# ALL_COMPONENTS.net
KiCad netlist of a schematic drawn in Altium Designer
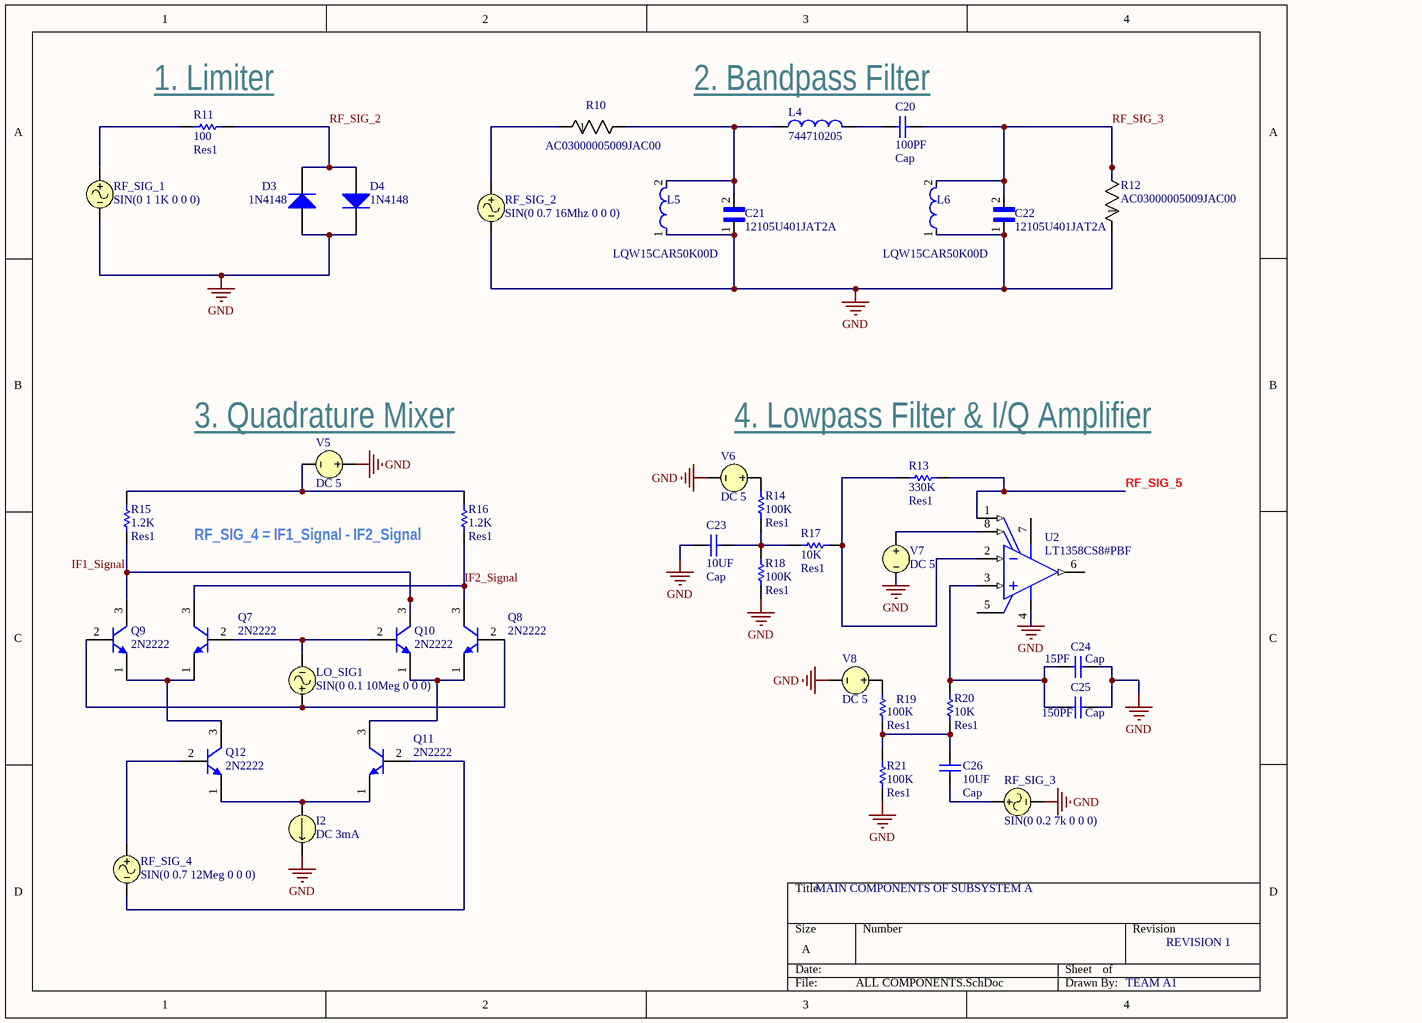
[diagram p0: ALL COMPONENTS.SchDoc]

(export (version "E")
  (design (tool "Eeschema 10.0.6"))
  (components
    (comp (ref "C20")
      (value "Cap")
      (footprint "RADIAL-0.1")
      (description "Capacitor")
      (fields
        (field (name "ALTIUM_VALUE") "100PF")
        (field (name "MANUFACTURER PART NUMBER") "K101K15C0GF53L2")
        (field (name "PUBLISHER") "Altium Limited")
      )
      (libsource (lib "ECE295-Capacitors-TH") (part "CAP CER 100PF 50V C0G/NP0 RADIAL"))
    )
    (comp (ref "C21")
      (value "12105U401JAT2A")
      (footprint "CAPC3224X140N")
      (description "CAP CER 400PF 50V 5% NP0 1210")
      (libsource (lib "12105U401JAT2A") (part "12105U401JAT2A"))
    )
    (comp (ref "C22")
      (value "12105U401JAT2A")
      (footprint "CAPC3224X140N")
      (description "CAP CER 400PF 50V 5% NP0 1210")
      (libsource (lib "12105U401JAT2A") (part "12105U401JAT2A"))
    )
    (comp (ref "C23")
      (value "Cap")
      (footprint "RADIAL-0.1")
      (description "Capacitor")
      (fields
        (field (name "ALTIUM_VALUE") "10UF")
        (field (name "MANUFACTURER PART NUMBER") "ESK106M063AC3FA")
        (field (name "PUBLISHER") "Altium Limited")
      )
      (libsource (lib "ECE295-Capacitors-TH") (part "CAP ALUM 10UF 20% 63V RADIAL"))
    )
    (comp (ref "C24")
      (value "Cap")
      (footprint "RADIAL-0.1")
      (description "Capacitor")
      (fields
        (field (name "ALTIUM_VALUE") "15PF")
        (field (name "MANUFACTURER PART NUMBER") "K150J15C0GF5TL2")
        (field (name "PUBLISHER") "Altium Limited")
      )
      (libsource (lib "ECE295-Capacitors-TH") (part "CAP CER 15PF 50V C0G/NP0 RADIAL"))
    )
    (comp (ref "C25")
      (value "Cap")
      (footprint "RADIAL-0.1")
      (description "Capacitor")
      (fields
        (field (name "ALTIUM_VALUE") "150PF")
        (field (name "MANUFACTURER PART NUMBER") "K151J15C0GF53L2")
        (field (name "PUBLISHER") "Altium Limited")
      )
      (libsource (lib "ECE295-Capacitors-TH") (part "CAP CER 150PF 50V C0G/NP0 RADIAL"))
    )
    (comp (ref "C26")
      (value "Cap")
      (footprint "RADIAL-0.1")
      (description "Capacitor")
      (fields
        (field (name "ALTIUM_VALUE") "10UF")
        (field (name "MANUFACTURER PART NUMBER") "ESK106M063AC3FA")
        (field (name "PUBLISHER") "Altium Limited")
      )
      (libsource (lib "ECE295-Capacitors-TH") (part "CAP ALUM 10UF 20% 63V RADIAL"))
    )
    (comp (ref "D3")
      (value "1N4148")
      (footprint "NXP-SOD27-2_V")
      (description "High-speed Diode, 100 V, 450 mA, 2-Pin SOD27, RoHS")
      (fields (field (name "MANUFACTURER") "NXP Semiconductors"))
      (libsource (lib "Altium Content Vault") (part "NXP-A1K2-2"))
    )
    (comp (ref "D4")
      (value "1N4148")
      (footprint "NXP-SOD27-2_V")
      (description "High-speed Diode, 100 V, 450 mA, 2-Pin SOD27, RoHS")
      (fields (field (name "MANUFACTURER") "NXP Semiconductors"))
      (libsource (lib "Altium Content Vault") (part "NXP-A1K2-2"))
    )
    (comp (ref "I2")
      (value "DC 3mA")
      (description "Current Source")
      (fields (field (name "PUBLISHER") "Altium Limited"))
      (libsource (lib "Simulation Generic Components") (part "ISRC"))
    )
    (comp (ref "L4")
      (value "744710205")
      (footprint "744710205")
      (fields (field (name "TOLERANCE") "25%"))
      (libsource (lib "Altium Content Vault") (part "Inductor - 1"))
    )
    (comp (ref "L5")
      (value "LQW15CAR50K00D")
      (footprint "FP-LQW15CA_00-MFG")
      (description "Wire Wound Ferrite Inductor for General Circuits 500nH ±10% 270mA 0.97Ω 0402 (1005)")
      (fields (field (name "TOLERANCE") "10%"))
      (libsource (lib "Altium Content Vault") (part "725321dda6339637d4d059423bc1c3c"))
    )
    (comp (ref "L6")
      (value "LQW15CAR50K00D")
      (footprint "FP-LQW15CA_00-MFG")
      (description "Wire Wound Ferrite Inductor for General Circuits 500nH ±10% 270mA 0.97Ω 0402 (1005)")
      (fields (field (name "TOLERANCE") "10%"))
      (libsource (lib "Altium Content Vault") (part "725321dda6339637d4d059423bc1c3c"))
    )
    (comp (ref "LO_SIG1")
      (value "SIN(0 0.1 10Meg 0 0 0)")
      (description "Sinusoidal Voltage Source")
      (fields (field (name "PUBLISHER") "Altium Limited"))
      (libsource (lib "Simulation Generic Components") (part "VSIN"))
    )
    (comp (ref "Q7")
      (value "2N2222")
      (footprint "MLTC-TO-18-3")
      (description "Low Power Bipolar NPN Transistor, 30 V, -65 to 200 degC, 3-Pin TO-18, RoHS, Bulk")
      (fields (field (name "MANUFACTURER") "Multicomp"))
      (libsource (lib "Altium Content Vault") (part "BJT-NPN-EBC-3"))
    )
    (comp (ref "Q8")
      (value "2N2222")
      (footprint "MLTC-TO-18-3")
      (description "Low Power Bipolar NPN Transistor, 30 V, -65 to 200 degC, 3-Pin TO-18, RoHS, Bulk")
      (fields (field (name "MANUFACTURER") "Multicomp"))
      (libsource (lib "Altium Content Vault") (part "BJT-NPN-EBC-3"))
    )
    (comp (ref "Q9")
      (value "2N2222")
      (footprint "MLTC-TO-18-3")
      (description "Low Power Bipolar NPN Transistor, 30 V, -65 to 200 degC, 3-Pin TO-18, RoHS, Bulk")
      (fields (field (name "MANUFACTURER") "Multicomp"))
      (libsource (lib "Altium Content Vault") (part "BJT-NPN-EBC-3"))
    )
    (comp (ref "Q10")
      (value "2N2222")
      (footprint "MLTC-TO-18-3")
      (description "Low Power Bipolar NPN Transistor, 30 V, -65 to 200 degC, 3-Pin TO-18, RoHS, Bulk")
      (fields (field (name "MANUFACTURER") "Multicomp"))
      (libsource (lib "Altium Content Vault") (part "BJT-NPN-EBC-3"))
    )
    (comp (ref "Q11")
      (value "2N2222")
      (footprint "MLTC-TO-18-3")
      (description "Low Power Bipolar NPN Transistor, 30 V, -65 to 200 degC, 3-Pin TO-18, RoHS, Bulk")
      (fields (field (name "MANUFACTURER") "Multicomp"))
      (libsource (lib "Altium Content Vault") (part "BJT-NPN-EBC-3"))
    )
    (comp (ref "Q12")
      (value "2N2222")
      (footprint "MLTC-TO-18-3")
      (description "Low Power Bipolar NPN Transistor, 30 V, -65 to 200 degC, 3-Pin TO-18, RoHS, Bulk")
      (fields (field (name "MANUFACTURER") "Multicomp"))
      (libsource (lib "Altium Content Vault") (part "BJT-NPN-EBC-3"))
    )
    (comp (ref "R10")
      (value "AC03000005009JAC00")
      (footprint "RES_AC03_VIS")
      (fields (field (name "TOLERANCE") "5%"))
      (libsource (lib "Altium Content Vault") (part "AC03000005009JAC00"))
    )
    (comp (ref "R11")
      (value "Res1")
      (footprint "AXIAL-0.1-RES")
      (description "Resistor")
      (fields
        (field (name "ALTIUM_VALUE") "100")
        (field (name "MANUFACTURER PART NUMBER") "CFR-25JB-52-100R")
        (field (name "TOLERANCE") "0.05")
        (field (name "PUBLISHER") "Altium Limited")
      )
      (libsource (lib "ECE295-Resistors-TH") (part "RES 100 OHM 5% 1/4W AXIAL"))
    )
    (comp (ref "R12")
      (value "AC03000005009JAC00")
      (footprint "RES_AC03_VIS")
      (fields (field (name "TOLERANCE") "5%"))
      (libsource (lib "Altium Content Vault") (part "AC03000005009JAC00"))
    )
    (comp (ref "R13")
      (value "Res1")
      (footprint "AXIAL-0.1-RES")
      (description "Resistor")
      (fields
        (field (name "ALTIUM_VALUE") "330K")
        (field (name "MANUFACTURER PART NUMBER") "CFR-25JB-52-330K")
        (field (name "TOLERANCE") "0.05")
        (field (name "PUBLISHER") "Altium Limited")
      )
      (libsource (lib "ECE295-Resistors-TH") (part "RES 330K OHM 5% 1/4W AXIAL"))
    )
    (comp (ref "R14")
      (value "Res1")
      (footprint "AXIAL-0.1-RES")
      (description "Resistor")
      (fields
        (field (name "ALTIUM_VALUE") "100K")
        (field (name "MANUFACTURER PART NUMBER") "CFR-25JB-52-100K")
        (field (name "TOLERANCE") "0.05")
        (field (name "PUBLISHER") "Altium Limited")
      )
      (libsource (lib "ECE295-Resistors-TH") (part "RES 100K OHM 5% 1/4W AXIAL"))
    )
    (comp (ref "R15")
      (value "Res1")
      (footprint "AXIAL-0.1-RES")
      (description "Resistor")
      (fields
        (field (name "ALTIUM_VALUE") "1.2K")
        (field (name "MANUFACTURER PART NUMBER") "CFR-25JB-52-1K2")
        (field (name "TOLERANCE") "0.05")
        (field (name "PUBLISHER") "Altium Limited")
      )
      (libsource (lib "ECE295-Resistors-TH") (part "RES 1.2K OHM 5% 1/4W AXIAL"))
    )
    (comp (ref "R16")
      (value "Res1")
      (footprint "AXIAL-0.1-RES")
      (description "Resistor")
      (fields
        (field (name "ALTIUM_VALUE") "1.2K")
        (field (name "MANUFACTURER PART NUMBER") "CFR-25JB-52-1K2")
        (field (name "TOLERANCE") "0.05")
        (field (name "PUBLISHER") "Altium Limited")
      )
      (libsource (lib "ECE295-Resistors-TH") (part "RES 1.2K OHM 5% 1/4W AXIAL"))
    )
    (comp (ref "R17")
      (value "Res1")
      (footprint "AXIAL-0.1-RES")
      (description "Resistor")
      (fields
        (field (name "ALTIUM_VALUE") "10K")
        (field (name "MANUFACTURER PART NUMBER") "CFR-25JB-52-10K")
        (field (name "TOLERANCE") "0.05")
        (field (name "PUBLISHER") "Altium Limited")
      )
      (libsource (lib "ECE295-Resistors-TH") (part "RES 10K OHM 5% 1/4W AXIAL"))
    )
    (comp (ref "R18")
      (value "Res1")
      (footprint "AXIAL-0.1-RES")
      (description "Resistor")
      (fields
        (field (name "ALTIUM_VALUE") "100K")
        (field (name "MANUFACTURER PART NUMBER") "CFR-25JB-52-100K")
        (field (name "TOLERANCE") "0.05")
        (field (name "PUBLISHER") "Altium Limited")
      )
      (libsource (lib "ECE295-Resistors-TH") (part "RES 100K OHM 5% 1/4W AXIAL"))
    )
    (comp (ref "R19")
      (value "Res1")
      (footprint "AXIAL-0.1-RES")
      (description "Resistor")
      (fields
        (field (name "ALTIUM_VALUE") "100K")
        (field (name "MANUFACTURER PART NUMBER") "CFR-25JB-52-100K")
        (field (name "TOLERANCE") "0.05")
        (field (name "PUBLISHER") "Altium Limited")
      )
      (libsource (lib "ECE295-Resistors-TH") (part "RES 100K OHM 5% 1/4W AXIAL"))
    )
    (comp (ref "R20")
      (value "Res1")
      (footprint "AXIAL-0.1-RES")
      (description "Resistor")
      (fields
        (field (name "ALTIUM_VALUE") "10K")
        (field (name "MANUFACTURER PART NUMBER") "CFR-25JB-52-10K")
        (field (name "TOLERANCE") "0.05")
        (field (name "PUBLISHER") "Altium Limited")
      )
      (libsource (lib "ECE295-Resistors-TH") (part "RES 10K OHM 5% 1/4W AXIAL"))
    )
    (comp (ref "R21")
      (value "Res1")
      (footprint "AXIAL-0.1-RES")
      (description "Resistor")
      (fields
        (field (name "ALTIUM_VALUE") "100K")
        (field (name "MANUFACTURER PART NUMBER") "CFR-25JB-52-100K")
        (field (name "TOLERANCE") "0.05")
        (field (name "PUBLISHER") "Altium Limited")
      )
      (libsource (lib "ECE295-Resistors-TH") (part "RES 100K OHM 5% 1/4W AXIAL"))
    )
    (comp (ref "RF_SIG_1")
      (value "SIN(0 1 1K 0 0 0)")
      (description "Sinusoidal Voltage Source")
      (fields (field (name "PUBLISHER") "Altium Limited"))
      (libsource (lib "Simulation Generic Components") (part "VSIN"))
    )
    (comp (ref "RF_SIG_2")
      (value "SIN(0 0.7 16Mhz 0 0 0)")
      (description "Sinusoidal Voltage Source")
      (fields (field (name "PUBLISHER") "Altium Limited"))
      (libsource (lib "Simulation Generic Components") (part "VSIN"))
    )
    (comp (ref "RF_SIG_3")
      (value "SIN(0 0.2 7k 0 0 0)")
      (description "Sinusoidal Voltage Source")
      (fields (field (name "PUBLISHER") "Altium Limited"))
      (libsource (lib "Simulation Generic Components") (part "VSIN"))
    )
    (comp (ref "RF_SIG_4")
      (value "SIN(0 0.7 12Meg 0 0 0)")
      (description "Sinusoidal Voltage Source")
      (fields (field (name "PUBLISHER") "Altium Limited"))
      (libsource (lib "Simulation Generic Components") (part "VSIN"))
    )
    (comp (ref "U2")
      (value "LT1358CS8#PBF")
      (footprint "LT-S8-8_M")
      (fields
        (field (name "MANUFACTURER") "Linear Technology")
        (field (name "LINEAR TECHNOLOGY PART NUMBER") "LT1358")
      )
      (libsource (lib "Altium Content Vault") (part "LT-LT135X-LT136X-8"))
    )
    (comp (ref "V5")
      (value "DC 5")
      (description "Voltage Source")
      (fields (field (name "PUBLISHER") "Altium Limited"))
      (libsource (lib "Simulation Generic Components") (part "VSRC"))
    )
    (comp (ref "V6")
      (value "DC 5")
      (description "Voltage Source")
      (fields (field (name "PUBLISHER") "Altium Limited"))
      (libsource (lib "Simulation Generic Components") (part "VSRC"))
    )
    (comp (ref "V7")
      (value "DC 5")
      (description "Voltage Source")
      (fields (field (name "PUBLISHER") "Altium Limited"))
      (libsource (lib "Simulation Generic Components") (part "VSRC"))
    )
    (comp (ref "V8")
      (value "DC 5")
      (description "Voltage Source")
      (fields (field (name "PUBLISHER") "Altium Limited"))
      (libsource (lib "Simulation Generic Components") (part "VSRC"))
    )
  )
  (nets
    (net (code "1") (name "/IF1_Signal") (class "Default")
      (node (ref "Q10") (pin "3") (pinfunction "C_3") (pintype "passive"))
      (node (ref "Q9") (pin "3") (pinfunction "C_3") (pintype "passive"))
      (node (ref "R15") (pin "1") (pinfunction "1_1") (pintype "passive"))
    )
    (net (code "2") (name "/IF2_Signal") (class "Default")
      (node (ref "Q7") (pin "3") (pinfunction "C_3") (pintype "passive"))
      (node (ref "Q8") (pin "3") (pinfunction "C_3") (pintype "passive"))
      (node (ref "R16") (pin "1") (pinfunction "1_1") (pintype "passive"))
    )
    (net (code "3") (name "/RF_SIG_2") (class "Default")
      (node (ref "D3") (pin "2") (pinfunction "K_2") (pintype "passive"))
      (node (ref "D4") (pin "1") (pinfunction "A_1") (pintype "passive"))
      (node (ref "R11") (pin "2") (pinfunction "2_2") (pintype "passive"))
    )
    (net (code "4") (name "/RF_SIG_3") (class "Default")
      (node (ref "C20") (pin "2") (pinfunction "2_2") (pintype "passive"))
      (node (ref "C22") (pin "2") (pinfunction "2_2") (pintype "passive"))
      (node (ref "L6") (pin "2") (pinfunction "2_2") (pintype "passive"))
      (node (ref "R12") (pin "2") (pinfunction "2_2") (pintype "passive"))
    )
    (net (code "5") (name "/RF_SIG_5") (class "Default")
      (node (ref "R13") (pin "2") (pinfunction "2_2") (pintype "passive"))
      (node (ref "U2") (pin "1") (pinfunction "NULL_1") (pintype "input"))
    )
    (net (code "6") (name "GND") (class "Default")
      (node (ref "C21") (pin "1") (pinfunction "1_1") (pintype "passive"))
      (node (ref "C22") (pin "1") (pinfunction "1_1") (pintype "passive"))
      (node (ref "C23") (pin "1") (pinfunction "1_1") (pintype "passive"))
      (node (ref "C24") (pin "2") (pinfunction "2_2") (pintype "passive"))
      (node (ref "C25") (pin "1") (pinfunction "1_1") (pintype "passive"))
      (node (ref "D3") (pin "1") (pinfunction "A_1") (pintype "passive"))
      (node (ref "D4") (pin "2") (pinfunction "K_2") (pintype "passive"))
      (node (ref "I2") (pin "2") (pinfunction "2_2") (pintype "passive"))
      (node (ref "L5") (pin "1") (pinfunction "1_1") (pintype "passive"))
      (node (ref "L6") (pin "1") (pinfunction "1_1") (pintype "passive"))
      (node (ref "R12") (pin "1") (pinfunction "1_1") (pintype "passive"))
      (node (ref "R18") (pin "1") (pinfunction "1_1") (pintype "passive"))
      (node (ref "R21") (pin "1") (pinfunction "1_1") (pintype "passive"))
      (node (ref "RF_SIG_1") (pin "2") (pinfunction "2_2") (pintype "passive"))
      (node (ref "RF_SIG_2") (pin "2") (pinfunction "2_2") (pintype "passive"))
      (node (ref "RF_SIG_3") (pin "2") (pinfunction "2_2") (pintype "passive"))
      (node (ref "U2") (pin "4") (pinfunction "V-_4") (pintype "power_in"))
      (node (ref "V5") (pin "1") (pinfunction "1_1") (pintype "passive"))
      (node (ref "V6") (pin "2") (pinfunction "2_2") (pintype "passive"))
      (node (ref "V7") (pin "2") (pinfunction "2_2") (pintype "passive"))
      (node (ref "V8") (pin "2") (pinfunction "2_2") (pintype "passive"))
    )
    (net (code "7") (name "Net-(C20-Pad1)") (class "Default")
      (node (ref "C20") (pin "1") (pinfunction "1_1") (pintype "passive"))
      (node (ref "L4") (pin "2") (pinfunction "2_2") (pintype "passive"))
    )
    (net (code "8") (name "Net-(C21-Pad2)") (class "Default")
      (node (ref "C21") (pin "2") (pinfunction "2_2") (pintype "passive"))
      (node (ref "L4") (pin "1") (pinfunction "1_1") (pintype "passive"))
      (node (ref "L5") (pin "2") (pinfunction "2_2") (pintype "passive"))
      (node (ref "R10") (pin "2") (pinfunction "2_2") (pintype "passive"))
    )
    (net (code "9") (name "Net-(C23-Pad2)") (class "Default")
      (node (ref "C23") (pin "2") (pinfunction "2_2") (pintype "passive"))
      (node (ref "R14") (pin "1") (pinfunction "1_1") (pintype "passive"))
      (node (ref "R17") (pin "1") (pinfunction "1_1") (pintype "passive"))
      (node (ref "R18") (pin "2") (pinfunction "2_2") (pintype "passive"))
    )
    (net (code "10") (name "Net-(C26-Pad1)") (class "Default")
      (node (ref "C26") (pin "1") (pinfunction "1_1") (pintype "passive"))
      (node (ref "RF_SIG_3") (pin "1") (pinfunction "1_1") (pintype "passive"))
    )
    (net (code "11") (name "Net-(C26-Pad2)") (class "Default")
      (node (ref "C26") (pin "2") (pinfunction "2_2") (pintype "passive"))
      (node (ref "R19") (pin "1") (pinfunction "1_1") (pintype "passive"))
      (node (ref "R20") (pin "1") (pinfunction "1_1") (pintype "passive"))
      (node (ref "R21") (pin "2") (pinfunction "2_2") (pintype "passive"))
    )
    (net (code "12") (name "Net-(Q8-B)") (class "Default")
      (node (ref "LO_SIG1") (pin "1") (pinfunction "1_1") (pintype "passive"))
      (node (ref "Q8") (pin "2") (pinfunction "B_2") (pintype "passive"))
      (node (ref "Q9") (pin "2") (pinfunction "B_2") (pintype "passive"))
    )
    (net (code "13") (name "Net-(Q10-B)") (class "Default")
      (node (ref "LO_SIG1") (pin "2") (pinfunction "2_2") (pintype "passive"))
      (node (ref "Q10") (pin "2") (pinfunction "B_2") (pintype "passive"))
      (node (ref "Q7") (pin "2") (pinfunction "B_2") (pintype "passive"))
    )
    (net (code "14") (name "Net-(Q10-E)") (class "Default")
      (node (ref "Q10") (pin "1") (pinfunction "E_1") (pintype "passive"))
      (node (ref "Q11") (pin "3") (pinfunction "C_3") (pintype "passive"))
      (node (ref "Q8") (pin "1") (pinfunction "E_1") (pintype "passive"))
    )
    (net (code "15") (name "Net-(Q11-B)") (class "Default")
      (node (ref "Q11") (pin "2") (pinfunction "B_2") (pintype "passive"))
      (node (ref "RF_SIG_4") (pin "2") (pinfunction "2_2") (pintype "passive"))
    )
    (net (code "16") (name "Net-(Q11-E)") (class "Default")
      (node (ref "I2") (pin "1") (pinfunction "1_1") (pintype "passive"))
      (node (ref "Q11") (pin "1") (pinfunction "E_1") (pintype "passive"))
      (node (ref "Q12") (pin "1") (pinfunction "E_1") (pintype "passive"))
    )
    (net (code "17") (name "Net-(Q12-B)") (class "Default")
      (node (ref "Q12") (pin "2") (pinfunction "B_2") (pintype "passive"))
      (node (ref "RF_SIG_4") (pin "1") (pinfunction "1_1") (pintype "passive"))
    )
    (net (code "18") (name "Net-(Q12-C)") (class "Default")
      (node (ref "Q12") (pin "3") (pinfunction "C_3") (pintype "passive"))
      (node (ref "Q7") (pin "1") (pinfunction "E_1") (pintype "passive"))
      (node (ref "Q9") (pin "1") (pinfunction "E_1") (pintype "passive"))
    )
    (net (code "19") (name "Net-(R10-Pad1)") (class "Default")
      (node (ref "R10") (pin "1") (pinfunction "1_1") (pintype "passive"))
      (node (ref "RF_SIG_2") (pin "1") (pinfunction "1_1") (pintype "passive"))
    )
    (net (code "20") (name "Net-(R11-Pad1)") (class "Default")
      (node (ref "R11") (pin "1") (pinfunction "1_1") (pintype "passive"))
      (node (ref "RF_SIG_1") (pin "1") (pinfunction "1_1") (pintype "passive"))
    )
    (net (code "21") (name "Net-(R14-Pad2)") (class "Default")
      (node (ref "R14") (pin "2") (pinfunction "2_2") (pintype "passive"))
      (node (ref "V6") (pin "1") (pinfunction "1_1") (pintype "passive"))
    )
    (net (code "22") (name "Net-(R15-Pad2)") (class "Default")
      (node (ref "R15") (pin "2") (pinfunction "2_2") (pintype "passive"))
      (node (ref "R16") (pin "2") (pinfunction "2_2") (pintype "passive"))
      (node (ref "V5") (pin "2") (pinfunction "2_2") (pintype "passive"))
    )
    (net (code "23") (name "Net-(R19-Pad2)") (class "Default")
      (node (ref "R19") (pin "2") (pinfunction "2_2") (pintype "passive"))
      (node (ref "V8") (pin "1") (pinfunction "1_1") (pintype "passive"))
    )
    (net (code "24") (name "Net-(U2-+IN)") (class "Default")
      (node (ref "C24") (pin "1") (pinfunction "1_1") (pintype "passive"))
      (node (ref "C25") (pin "2") (pinfunction "2_2") (pintype "passive"))
      (node (ref "R20") (pin "2") (pinfunction "2_2") (pintype "passive"))
      (node (ref "U2") (pin "3") (pinfunction "+IN_3") (pintype "input"))
    )
    (net (code "25") (name "Net-(U2--IN)") (class "Default")
      (node (ref "R13") (pin "1") (pinfunction "1_1") (pintype "passive"))
      (node (ref "R17") (pin "2") (pinfunction "2_2") (pintype "passive"))
      (node (ref "U2") (pin "2") (pinfunction "-IN_2") (pintype "input"))
    )
    (net (code "26") (name "Net-(U2-NULL-Pad8)") (class "Default")
      (node (ref "U2") (pin "8") (pinfunction "NULL_8") (pintype "input"))
      (node (ref "V7") (pin "1") (pinfunction "1_1") (pintype "passive"))
    )
    (net (code "27") (name "unconnected-(U2-NC-Pad5)") (class "Default")
      (node (ref "U2") (pin "5") (pinfunction "NC_5") (pintype "passive"))
    )
    (net (code "28") (name "unconnected-(U2-V+-Pad7)") (class "Default")
      (node (ref "U2") (pin "7") (pinfunction "V+_7") (pintype "power_in"))
    )
    (net (code "29") (name "unconnected-(U2-VOUT-Pad6)") (class "Default")
      (node (ref "U2") (pin "6") (pinfunction "VOUT_6") (pintype "output"))
    )
  )
)
